# RadioMusic.net
KiCad netlist of a schematic drawn in EAGLE
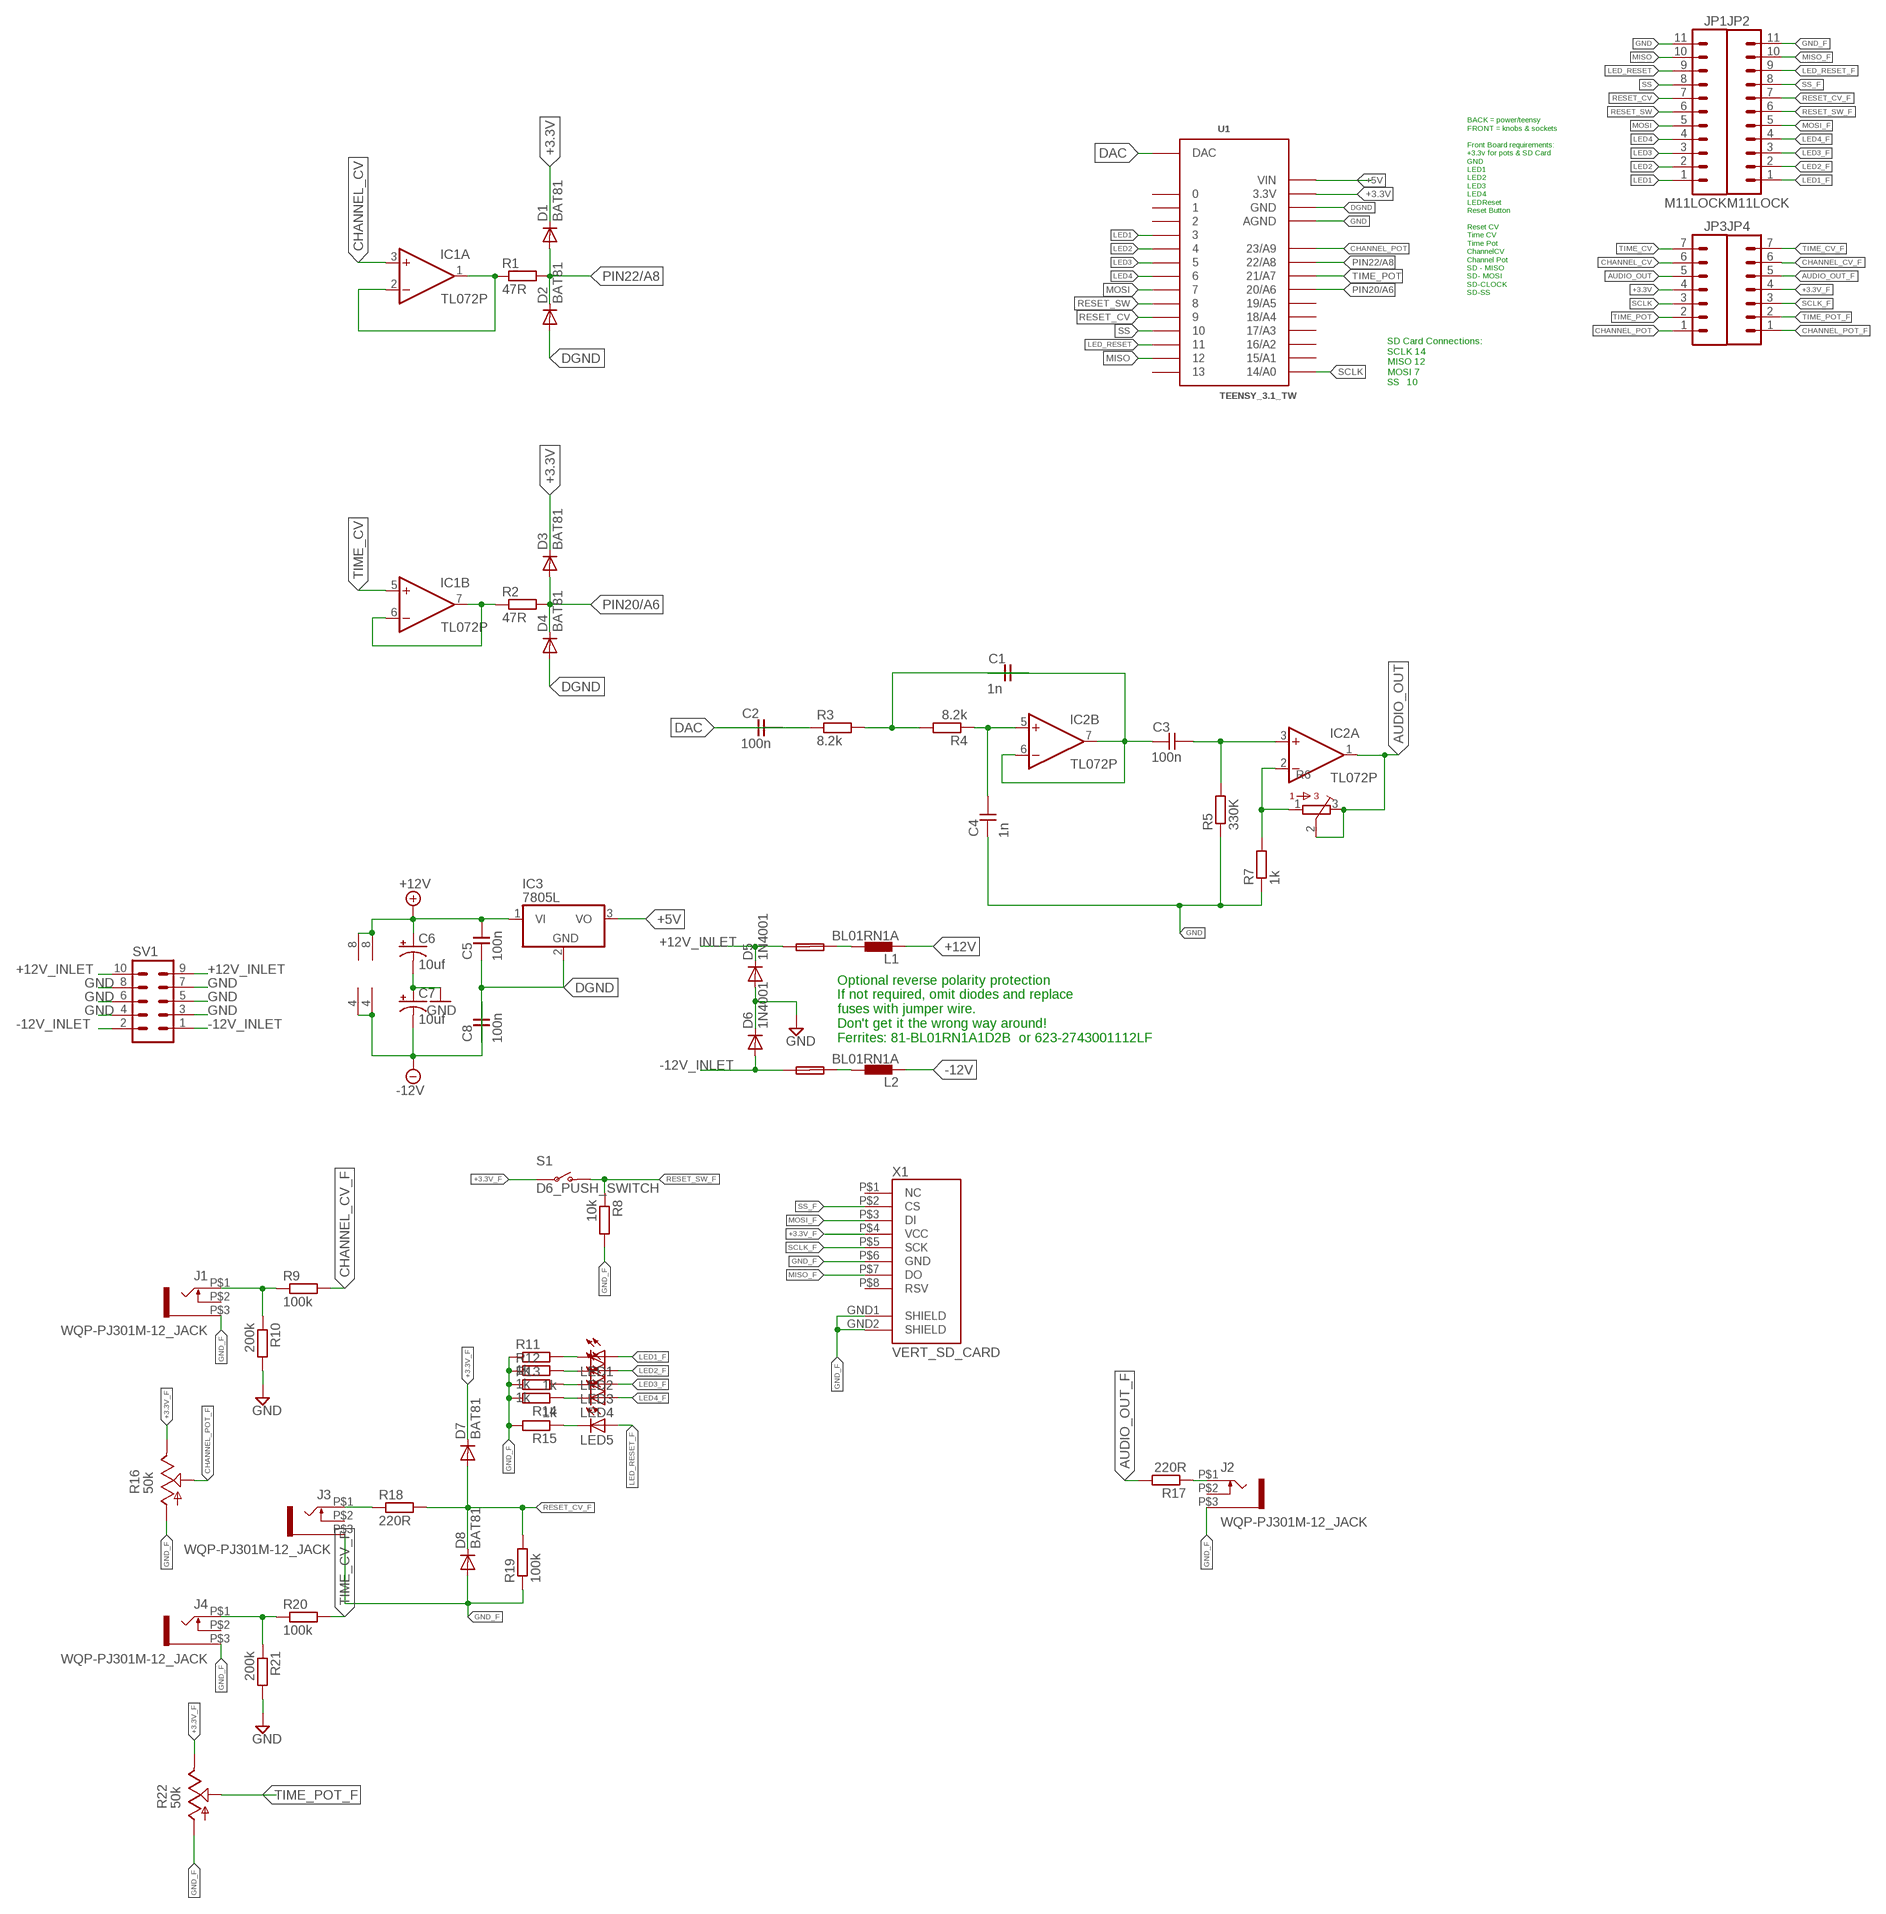
[diagram p0: schematic, sheet 1]

(export (version "E")
  (design (tool "Eeschema 10.0.6"))
  (components
    (comp (ref "C1")
      (value "1n")
      (footprint "eagle-import:C050-024X044")
      (libsource (lib "eagle-import") (part "C-EU050-024X044"))
    )
    (comp (ref "C2")
      (value "100n")
      (footprint "eagle-import:C050-025X075")
      (libsource (lib "eagle-import") (part "C-EU050-025X075"))
    )
    (comp (ref "C3")
      (value "100n")
      (footprint "eagle-import:C050-025X075")
      (libsource (lib "eagle-import") (part "C-EU050-025X075"))
    )
    (comp (ref "C4")
      (value "1n")
      (footprint "eagle-import:C050-024X044")
      (libsource (lib "eagle-import") (part "C-EU050-024X044"))
    )
    (comp (ref "C5")
      (value "100n")
      (footprint "eagle-import:C050-024X044")
      (libsource (lib "eagle-import") (part "C-EU050-024X044"))
    )
    (comp (ref "C6")
      (value "10uf")
      (footprint "eagle-import:CPOL-RADIAL-10UF-25V")
      (libsource (lib "eagle-import") (part "CAP_POLPTH2"))
    )
    (comp (ref "C7")
      (value "10uf")
      (footprint "eagle-import:CPOL-RADIAL-10UF-25V")
      (libsource (lib "eagle-import") (part "CAP_POLPTH2"))
    )
    (comp (ref "C8")
      (value "100n")
      (footprint "eagle-import:C050-024X044")
      (libsource (lib "eagle-import") (part "C-EU050-024X044"))
    )
    (comp (ref "D1")
      (value "BAT81")
      (footprint "eagle-import:DO34-7")
      (libsource (lib "eagle-import") (part "BAT81"))
    )
    (comp (ref "D2")
      (value "BAT81")
      (footprint "eagle-import:DO34-7")
      (libsource (lib "eagle-import") (part "BAT81"))
    )
    (comp (ref "D3")
      (value "BAT81")
      (footprint "eagle-import:DO34-7")
      (libsource (lib "eagle-import") (part "BAT81"))
    )
    (comp (ref "D4")
      (value "BAT81")
      (footprint "eagle-import:DO34-7")
      (libsource (lib "eagle-import") (part "BAT81"))
    )
    (comp (ref "D5")
      (value "1N4001")
      (footprint "eagle-import:DO41-10")
      (libsource (lib "eagle-import") (part "1N4004"))
    )
    (comp (ref "D6")
      (value "1N4001")
      (footprint "eagle-import:DO41-10")
      (libsource (lib "eagle-import") (part "1N4004"))
    )
    (comp (ref "D7")
      (value "BAT81")
      (footprint "eagle-import:DO34-7")
      (libsource (lib "eagle-import") (part "BAT81"))
    )
    (comp (ref "D8")
      (value "BAT81")
      (footprint "eagle-import:DO34-7")
      (libsource (lib "eagle-import") (part "BAT81"))
    )
    (comp (ref "F1")
      (value "FUSE")
      (footprint "eagle-import:C050H075X075")
      (libsource (lib "eagle-import") (part "PTC_FUSEPOLY_FUSE"))
    )
    (comp (ref "F2")
      (value "FUSE")
      (footprint "eagle-import:C050H075X075")
      (libsource (lib "eagle-import") (part "PTC_FUSEPOLY_FUSE"))
    )
    (comp (ref "IC1")
      (value "TL072P")
      (footprint "eagle-import:DIL08")
      (libsource (lib "eagle-import") (part "TL072P"))
    )
    (comp (ref "IC2")
      (value "TL072P")
      (footprint "eagle-import:DIL08")
      (libsource (lib "eagle-import") (part "TL072P"))
    )
    (comp (ref "IC3")
      (value "7805L")
      (footprint "eagle-import:TO92")
      (libsource (lib "eagle-import") (part "78L05"))
    )
    (comp (ref "J1")
      (value "WQP-PJ301M-12_JACK")
      (footprint "eagle-import:WQP-PJ301M-12_JACK")
      (libsource (lib "eagle-import") (part "WQP-PJ301M-12_JACK"))
    )
    (comp (ref "J2")
      (value "WQP-PJ301M-12_JACK")
      (footprint "eagle-import:WQP-PJ301M-12_JACK")
      (libsource (lib "eagle-import") (part "WQP-PJ301M-12_JACK"))
    )
    (comp (ref "J3")
      (value "WQP-PJ301M-12_JACK")
      (footprint "eagle-import:WQP-PJ301M-12_JACK")
      (libsource (lib "eagle-import") (part "WQP-PJ301M-12_JACK"))
    )
    (comp (ref "J4")
      (value "WQP-PJ301M-12_JACK")
      (footprint "eagle-import:WQP-PJ301M-12_JACK")
      (libsource (lib "eagle-import") (part "WQP-PJ301M-12_JACK"))
    )
    (comp (ref "JP1")
      (value "M11LOCK")
      (footprint "eagle-import:1X11_LOCK")
      (libsource (lib "eagle-import") (part "M11LOCK"))
    )
    (comp (ref "JP2")
      (value "M11LOCK")
      (footprint "eagle-import:1X11_LOCK")
      (libsource (lib "eagle-import") (part "M11LOCK"))
    )
    (comp (ref "JP3")
      (value "M07LOCK")
      (footprint "eagle-import:1X07_LOCK")
      (libsource (lib "eagle-import") (part "M07LOCK"))
    )
    (comp (ref "JP4")
      (value "M07LOCK")
      (footprint "eagle-import:1X07_LOCK")
      (libsource (lib "eagle-import") (part "M07LOCK"))
    )
    (comp (ref "L1")
      (value "BL01RN1A")
      (footprint "eagle-import:BL01RN1A")
      (libsource (lib "eagle-import") (part "BL01RN1A"))
    )
    (comp (ref "L2")
      (value "BL01RN1A")
      (footprint "eagle-import:BL01RN1A")
      (libsource (lib "eagle-import") (part "BL01RN1A"))
    )
    (comp (ref "LED1")
      (value "LED3MM")
      (footprint "eagle-import:LED3MM")
      (libsource (lib "eagle-import") (part "LED3MM"))
    )
    (comp (ref "LED2")
      (value "LED3MM")
      (footprint "eagle-import:LED3MM")
      (libsource (lib "eagle-import") (part "LED3MM"))
    )
    (comp (ref "LED3")
      (value "LED3MM")
      (footprint "eagle-import:LED3MM")
      (libsource (lib "eagle-import") (part "LED3MM"))
    )
    (comp (ref "LED4")
      (value "LED3MM")
      (footprint "eagle-import:LED3MM")
      (libsource (lib "eagle-import") (part "LED3MM"))
    )
    (comp (ref "LED5")
      (value "LED3MM")
      (footprint "eagle-import:LED3MM")
      (libsource (lib "eagle-import") (part "LED3MM"))
    )
    (comp (ref "R1")
      (value "47R")
      (footprint "eagle-import:0207_10")
      (libsource (lib "eagle-import") (part "R-EU_STANDARD_RESISTOR"))
    )
    (comp (ref "R2")
      (value "47R")
      (footprint "eagle-import:0207_10")
      (libsource (lib "eagle-import") (part "R-EU_STANDARD_RESISTOR"))
    )
    (comp (ref "R3")
      (value "8.2k")
      (footprint "eagle-import:0207_10")
      (libsource (lib "eagle-import") (part "R-EU_STANDARD_RESISTOR"))
    )
    (comp (ref "R4")
      (value "8.2k")
      (footprint "eagle-import:0207_10")
      (libsource (lib "eagle-import") (part "R-EU_STANDARD_RESISTOR"))
    )
    (comp (ref "R5")
      (value "330K")
      (footprint "eagle-import:0207_10")
      (libsource (lib "eagle-import") (part "R-EU_STANDARD_RESISTOR"))
    )
    (comp (ref "R6")
      (value "3362P")
      (footprint "eagle-import:3362P")
      (libsource (lib "eagle-import") (part "3362P"))
    )
    (comp (ref "R7")
      (value "1k")
      (footprint "eagle-import:0207_10")
      (libsource (lib "eagle-import") (part "R-EU_STANDARD_RESISTOR"))
    )
    (comp (ref "R8")
      (value "10k")
      (footprint "eagle-import:0207_10")
      (libsource (lib "eagle-import") (part "R-EU_STANDARD_RESISTOR"))
    )
    (comp (ref "R9")
      (value "100k")
      (footprint "eagle-import:0207_10")
      (libsource (lib "eagle-import") (part "R-EU_STANDARD_RESISTOR"))
    )
    (comp (ref "R10")
      (value "200k")
      (footprint "eagle-import:0207_10")
      (libsource (lib "eagle-import") (part "R-EU_STANDARD_RESISTOR"))
    )
    (comp (ref "R11")
      (value "1k")
      (footprint "eagle-import:0207_10")
      (libsource (lib "eagle-import") (part "R-EU_STANDARD_RESISTOR"))
    )
    (comp (ref "R12")
      (value "1k")
      (footprint "eagle-import:0207_10")
      (libsource (lib "eagle-import") (part "R-EU_STANDARD_RESISTOR"))
    )
    (comp (ref "R13")
      (value "1k")
      (footprint "eagle-import:0207_10")
      (libsource (lib "eagle-import") (part "R-EU_STANDARD_RESISTOR"))
    )
    (comp (ref "R14")
      (value "1k")
      (footprint "eagle-import:0207_10")
      (libsource (lib "eagle-import") (part "R-EU_STANDARD_RESISTOR"))
    )
    (comp (ref "R15")
      (value "1k")
      (footprint "eagle-import:0207_10")
      (libsource (lib "eagle-import") (part "R-EU_STANDARD_RESISTOR"))
    )
    (comp (ref "R16")
      (value "50k")
      (footprint "eagle-import:EVUF")
      (libsource (lib "eagle-import") (part "ALPHA-9MMAF2"))
    )
    (comp (ref "R17")
      (value "220R")
      (footprint "eagle-import:0207_10")
      (libsource (lib "eagle-import") (part "R-EU_STANDARD_RESISTOR"))
    )
    (comp (ref "R18")
      (value "220R")
      (footprint "eagle-import:0207_10")
      (libsource (lib "eagle-import") (part "R-EU_STANDARD_RESISTOR"))
    )
    (comp (ref "R19")
      (value "100k")
      (footprint "eagle-import:0207_10")
      (libsource (lib "eagle-import") (part "R-EU_STANDARD_RESISTOR"))
    )
    (comp (ref "R20")
      (value "100k")
      (footprint "eagle-import:0207_10")
      (libsource (lib "eagle-import") (part "R-EU_STANDARD_RESISTOR"))
    )
    (comp (ref "R21")
      (value "200k")
      (footprint "eagle-import:0207_10")
      (libsource (lib "eagle-import") (part "R-EU_STANDARD_RESISTOR"))
    )
    (comp (ref "R22")
      (value "50k")
      (footprint "eagle-import:EVUF")
      (libsource (lib "eagle-import") (part "ALPHA-9MMAF2"))
    )
    (comp (ref "S1")
      (value "D6_PUSH_SWITCH")
      (footprint "eagle-import:D6_BUTTON_RND")
      (libsource (lib "eagle-import") (part "D6_PUSH_SWITCH"))
    )
    (comp (ref "SV1")
      (value "10_PIN_HEADER")
      (footprint "eagle-import:MA05-2")
      (libsource (lib "eagle-import") (part "10_PIN_HEADER"))
    )
    (comp (ref "U1")
      (value "TEENSY_3.1_TW")
      (footprint "eagle-import:TEENSY_3.1_TW")
      (libsource (lib "eagle-import") (part "TEENSY_3.1_TW"))
    )
    (comp (ref "X1")
      (value "VERT_SD_CARD")
      (footprint "eagle-import:VERT_MICROSD")
      (libsource (lib "eagle-import") (part "VERT_SD_CARD"))
    )
  )
  (nets
    (net (code "1") (name "+3.3V") (class "Default")
      (node (ref "D1") (pin "C") (pinfunction "C_C") (pintype "passive"))
      (node (ref "D3") (pin "C") (pinfunction "C_C") (pintype "passive"))
      (node (ref "JP3") (pin "4") (pinfunction "4_4") (pintype "passive"))
      (node (ref "U1") (pin "3.3V") (pinfunction "3.3V_3.3V") (pintype "power_in"))
    )
    (net (code "2") (name "+3.3V_F") (class "Default")
      (node (ref "D7") (pin "C") (pinfunction "C_C") (pintype "passive"))
      (node (ref "JP4") (pin "4") (pinfunction "4_4") (pintype "passive"))
      (node (ref "R16") (pin "3") (pinfunction "E_3") (pintype "passive"))
      (node (ref "R22") (pin "3") (pinfunction "E_3") (pintype "passive"))
      (node (ref "S1") (pin "P$3") (pinfunction "P_P$3") (pintype "passive"))
      (node (ref "S1") (pin "P$4") (pinfunction "P_P$4") (pintype "passive"))
      (node (ref "X1") (pin "P$4") (pinfunction "VCC_P$4") (pintype "bidirectional"))
    )
    (net (code "3") (name "+5V") (class "Default")
      (node (ref "IC3") (pin "3") (pinfunction "VO_3") (pintype "passive"))
      (node (ref "U1") (pin "VIN") (pinfunction "VIN_VIN") (pintype "power_in"))
    )
    (net (code "4") (name "+12V") (class "Default")
      (node (ref "C5") (pin "1") (pinfunction "1_1") (pintype "passive"))
      (node (ref "C6") (pin "1") (pinfunction "+_1") (pintype "passive"))
      (node (ref "IC1") (pin "8") (pinfunction "V+_8") (pintype "power_in"))
      (node (ref "IC2") (pin "8") (pinfunction "V+_8") (pintype "power_in"))
      (node (ref "IC3") (pin "1") (pinfunction "VI_1") (pintype "input"))
      (node (ref "L1") (pin "1") (pinfunction "1_1") (pintype "passive"))
    )
    (net (code "5") (name "-12V") (class "Default")
      (node (ref "C7") (pin "2") (pinfunction "-_2") (pintype "passive"))
      (node (ref "C8") (pin "1") (pinfunction "1_1") (pintype "passive"))
      (node (ref "IC1") (pin "4") (pinfunction "V-_4") (pintype "power_in"))
      (node (ref "IC2") (pin "4") (pinfunction "V-_4") (pintype "power_in"))
      (node (ref "L2") (pin "1") (pinfunction "1_1") (pintype "passive"))
    )
    (net (code "6") (name "/+12V_INLET") (class "Default")
      (node (ref "D5") (pin "C") (pinfunction "C_C") (pintype "passive"))
      (node (ref "F1") (pin "1") (pinfunction "P$1_1") (pintype "bidirectional"))
      (node (ref "SV1") (pin "10") (pinfunction "10_10") (pintype "passive"))
      (node (ref "SV1") (pin "9") (pinfunction "9_9") (pintype "passive"))
    )
    (net (code "7") (name "/-12V_INLET") (class "Default")
      (node (ref "D6") (pin "A") (pinfunction "A_A") (pintype "passive"))
      (node (ref "F2") (pin "1") (pinfunction "P$1_1") (pintype "bidirectional"))
      (node (ref "SV1") (pin "1") (pinfunction "1_1") (pintype "passive"))
      (node (ref "SV1") (pin "2") (pinfunction "2_2") (pintype "passive"))
    )
    (net (code "8") (name "AUDIO_OUT") (class "Default")
      (node (ref "IC2") (pin "1") (pinfunction "OUT_1") (pintype "output"))
      (node (ref "JP3") (pin "5") (pinfunction "5_5") (pintype "passive"))
      (node (ref "R6") (pin "2") (pinfunction "2_2") (pintype "passive"))
      (node (ref "R6") (pin "3") (pinfunction "3_3") (pintype "passive"))
    )
    (net (code "9") (name "AUDIO_OUT_F") (class "Default")
      (node (ref "JP4") (pin "5") (pinfunction "5_5") (pintype "passive"))
      (node (ref "R17") (pin "2") (pinfunction "2_2") (pintype "passive"))
    )
    (net (code "10") (name "CHANNEL_CV") (class "Default")
      (node (ref "IC1") (pin "3") (pinfunction "+IN_3") (pintype "input"))
      (node (ref "JP3") (pin "6") (pinfunction "6_6") (pintype "passive"))
    )
    (net (code "11") (name "CHANNEL_CV_F") (class "Default")
      (node (ref "JP4") (pin "6") (pinfunction "6_6") (pintype "passive"))
      (node (ref "R9") (pin "2") (pinfunction "2_2") (pintype "passive"))
    )
    (net (code "12") (name "CHANNEL_POT") (class "Default")
      (node (ref "JP3") (pin "1") (pinfunction "1_1") (pintype "passive"))
      (node (ref "U1") (pin "23/A9") (pinfunction "23/A9_23/A9") (pintype "bidirectional"))
    )
    (net (code "13") (name "CHANNEL_POT_F") (class "Default")
      (node (ref "JP4") (pin "1") (pinfunction "1_1") (pintype "passive"))
      (node (ref "R16") (pin "2") (pinfunction "S_2") (pintype "passive"))
    )
    (net (code "14") (name "DAC") (class "Default")
      (node (ref "C2") (pin "1") (pinfunction "1_1") (pintype "passive"))
      (node (ref "U1") (pin "DAC") (pinfunction "DAC_DAC") (pintype "bidirectional"))
    )
    (net (code "15") (name "DGND") (class "Default")
      (node (ref "C5") (pin "2") (pinfunction "2_2") (pintype "passive"))
      (node (ref "C8") (pin "2") (pinfunction "2_2") (pintype "passive"))
      (node (ref "D2") (pin "A") (pinfunction "A_A") (pintype "passive"))
      (node (ref "D4") (pin "A") (pinfunction "A_A") (pintype "passive"))
      (node (ref "IC3") (pin "2") (pinfunction "GND_2") (pintype "passive"))
      (node (ref "U1") (pin "GND") (pinfunction "GND_GND") (pintype "power_in"))
    )
    (net (code "16") (name "GND") (class "Default")
      (node (ref "C4") (pin "2") (pinfunction "2_2") (pintype "passive"))
      (node (ref "C6") (pin "2") (pinfunction "-_2") (pintype "passive"))
      (node (ref "C7") (pin "1") (pinfunction "+_1") (pintype "passive"))
      (node (ref "D5") (pin "A") (pinfunction "A_A") (pintype "passive"))
      (node (ref "D6") (pin "C") (pinfunction "C_C") (pintype "passive"))
      (node (ref "JP1") (pin "11") (pinfunction "11_11") (pintype "passive"))
      (node (ref "R10") (pin "2") (pinfunction "2_2") (pintype "passive"))
      (node (ref "R21") (pin "2") (pinfunction "2_2") (pintype "passive"))
      (node (ref "R5") (pin "1") (pinfunction "1_1") (pintype "passive"))
      (node (ref "R7") (pin "1") (pinfunction "1_1") (pintype "passive"))
      (node (ref "SV1") (pin "3") (pinfunction "3_3") (pintype "passive"))
      (node (ref "SV1") (pin "4") (pinfunction "4_4") (pintype "passive"))
      (node (ref "SV1") (pin "5") (pinfunction "5_5") (pintype "passive"))
      (node (ref "SV1") (pin "6") (pinfunction "6_6") (pintype "passive"))
      (node (ref "SV1") (pin "7") (pinfunction "7_7") (pintype "passive"))
      (node (ref "SV1") (pin "8") (pinfunction "8_8") (pintype "passive"))
      (node (ref "U1") (pin "AGND") (pinfunction "AGND_AGND") (pintype "power_in"))
    )
    (net (code "17") (name "GND_F") (class "Default")
      (node (ref "D8") (pin "A") (pinfunction "A_A") (pintype "passive"))
      (node (ref "J1") (pin "P$3") (pinfunction "1_P$3") (pintype "passive"))
      (node (ref "J2") (pin "P$3") (pinfunction "1_P$3") (pintype "passive"))
      (node (ref "J3") (pin "P$3") (pinfunction "1_P$3") (pintype "passive"))
      (node (ref "J4") (pin "P$3") (pinfunction "1_P$3") (pintype "passive"))
      (node (ref "JP2") (pin "11") (pinfunction "11_11") (pintype "passive"))
      (node (ref "R11") (pin "1") (pinfunction "1_1") (pintype "passive"))
      (node (ref "R12") (pin "1") (pinfunction "1_1") (pintype "passive"))
      (node (ref "R13") (pin "1") (pinfunction "1_1") (pintype "passive"))
      (node (ref "R14") (pin "2") (pinfunction "2_2") (pintype "passive"))
      (node (ref "R15") (pin "2") (pinfunction "2_2") (pintype "passive"))
      (node (ref "R16") (pin "1") (pinfunction "A_1") (pintype "passive"))
      (node (ref "R19") (pin "1") (pinfunction "1_1") (pintype "passive"))
      (node (ref "R22") (pin "1") (pinfunction "A_1") (pintype "passive"))
      (node (ref "R8") (pin "2") (pinfunction "2_2") (pintype "passive"))
      (node (ref "X1") (pin "GND1") (pinfunction "SHIELD_GND1") (pintype "bidirectional"))
      (node (ref "X1") (pin "GND2") (pinfunction "SHIELD_GND2") (pintype "bidirectional"))
      (node (ref "X1") (pin "P$6") (pinfunction "GND_P$6") (pintype "bidirectional"))
    )
    (net (code "18") (name "LED1") (class "Default")
      (node (ref "JP1") (pin "1") (pinfunction "1_1") (pintype "passive"))
      (node (ref "U1") (pin "3") (pinfunction "3_3") (pintype "bidirectional"))
    )
    (net (code "19") (name "LED1_F") (class "Default")
      (node (ref "JP2") (pin "1") (pinfunction "1_1") (pintype "passive"))
      (node (ref "LED1") (pin "A") (pinfunction "A_A") (pintype "passive"))
    )
    (net (code "20") (name "LED2") (class "Default")
      (node (ref "JP1") (pin "2") (pinfunction "2_2") (pintype "passive"))
      (node (ref "U1") (pin "4") (pinfunction "4_4") (pintype "bidirectional"))
    )
    (net (code "21") (name "LED2_F") (class "Default")
      (node (ref "JP2") (pin "2") (pinfunction "2_2") (pintype "passive"))
      (node (ref "LED2") (pin "A") (pinfunction "A_A") (pintype "passive"))
    )
    (net (code "22") (name "LED3") (class "Default")
      (node (ref "JP1") (pin "3") (pinfunction "3_3") (pintype "passive"))
      (node (ref "U1") (pin "5") (pinfunction "5_5") (pintype "bidirectional"))
    )
    (net (code "23") (name "LED3_F") (class "Default")
      (node (ref "JP2") (pin "3") (pinfunction "3_3") (pintype "passive"))
      (node (ref "LED3") (pin "A") (pinfunction "A_A") (pintype "passive"))
    )
    (net (code "24") (name "LED4") (class "Default")
      (node (ref "JP1") (pin "4") (pinfunction "4_4") (pintype "passive"))
      (node (ref "U1") (pin "6") (pinfunction "6_6") (pintype "bidirectional"))
    )
    (net (code "25") (name "LED4_F") (class "Default")
      (node (ref "JP2") (pin "4") (pinfunction "4_4") (pintype "passive"))
      (node (ref "LED4") (pin "A") (pinfunction "A_A") (pintype "passive"))
    )
    (net (code "26") (name "LED_RESET") (class "Default")
      (node (ref "JP1") (pin "9") (pinfunction "9_9") (pintype "passive"))
      (node (ref "U1") (pin "11") (pinfunction "11_11") (pintype "bidirectional"))
    )
    (net (code "27") (name "LED_RESET_F") (class "Default")
      (node (ref "JP2") (pin "9") (pinfunction "9_9") (pintype "passive"))
      (node (ref "LED5") (pin "A") (pinfunction "A_A") (pintype "passive"))
    )
    (net (code "28") (name "MISO") (class "Default")
      (node (ref "JP1") (pin "10") (pinfunction "10_10") (pintype "passive"))
      (node (ref "U1") (pin "12") (pinfunction "12_12") (pintype "bidirectional"))
    )
    (net (code "29") (name "MISO_F") (class "Default")
      (node (ref "JP2") (pin "10") (pinfunction "10_10") (pintype "passive"))
      (node (ref "X1") (pin "P$7") (pinfunction "DO_P$7") (pintype "bidirectional"))
    )
    (net (code "30") (name "MOSI") (class "Default")
      (node (ref "JP1") (pin "5") (pinfunction "5_5") (pintype "passive"))
      (node (ref "U1") (pin "7") (pinfunction "7_7") (pintype "bidirectional"))
    )
    (net (code "31") (name "MOSI_F") (class "Default")
      (node (ref "JP2") (pin "5") (pinfunction "5_5") (pintype "passive"))
      (node (ref "X1") (pin "P$3") (pinfunction "DI_P$3") (pintype "bidirectional"))
    )
    (net (code "32") (name "Net-(C1-Pad1)") (class "Default")
      (node (ref "C1") (pin "1") (pinfunction "1_1") (pintype "passive"))
      (node (ref "R3") (pin "2") (pinfunction "2_2") (pintype "passive"))
      (node (ref "R4") (pin "2") (pinfunction "2_2") (pintype "passive"))
    )
    (net (code "33") (name "Net-(C2-Pad2)") (class "Default")
      (node (ref "C2") (pin "2") (pinfunction "2_2") (pintype "passive"))
      (node (ref "R3") (pin "1") (pinfunction "1_1") (pintype "passive"))
    )
    (net (code "34") (name "Net-(F1-P$2)") (class "Default")
      (node (ref "F1") (pin "2") (pinfunction "P$2_2") (pintype "bidirectional"))
      (node (ref "L1") (pin "2") (pinfunction "2_2") (pintype "passive"))
    )
    (net (code "35") (name "Net-(F2-P$2)") (class "Default")
      (node (ref "F2") (pin "2") (pinfunction "P$2_2") (pintype "bidirectional"))
      (node (ref "L2") (pin "2") (pinfunction "2_2") (pintype "passive"))
    )
    (net (code "36") (name "Net-(IC1B--IN)") (class "Default")
      (node (ref "IC1") (pin "6") (pinfunction "-IN_6") (pintype "input"))
      (node (ref "IC1") (pin "7") (pinfunction "OUT_7") (pintype "output"))
      (node (ref "R2") (pin "1") (pinfunction "1_1") (pintype "passive"))
    )
    (net (code "37") (name "Net-(IC2A-+IN)") (class "Default")
      (node (ref "C3") (pin "1") (pinfunction "1_1") (pintype "passive"))
      (node (ref "IC2") (pin "3") (pinfunction "+IN_3") (pintype "input"))
      (node (ref "R5") (pin "2") (pinfunction "2_2") (pintype "passive"))
    )
    (net (code "38") (name "Net-(IC2A--IN)") (class "Default")
      (node (ref "IC2") (pin "2") (pinfunction "-IN_2") (pintype "input"))
      (node (ref "R6") (pin "1") (pinfunction "1_1") (pintype "passive"))
      (node (ref "R7") (pin "2") (pinfunction "2_2") (pintype "passive"))
    )
    (net (code "39") (name "Net-(IC2B-+IN)") (class "Default")
      (node (ref "C4") (pin "1") (pinfunction "1_1") (pintype "passive"))
      (node (ref "IC2") (pin "5") (pinfunction "+IN_5") (pintype "input"))
      (node (ref "R4") (pin "1") (pinfunction "1_1") (pintype "passive"))
    )
    (net (code "40") (name "Net-(IC2B--IN)") (class "Default")
      (node (ref "C1") (pin "2") (pinfunction "2_2") (pintype "passive"))
      (node (ref "C3") (pin "2") (pinfunction "2_2") (pintype "passive"))
      (node (ref "IC2") (pin "6") (pinfunction "-IN_6") (pintype "input"))
      (node (ref "IC2") (pin "7") (pinfunction "OUT_7") (pintype "output"))
    )
    (net (code "41") (name "Net-(J1-2)") (class "Default")
      (node (ref "J1") (pin "P$1") (pinfunction "2_P$1") (pintype "passive"))
      (node (ref "R10") (pin "1") (pinfunction "1_1") (pintype "passive"))
      (node (ref "R9") (pin "1") (pinfunction "1_1") (pintype "passive"))
    )
    (net (code "42") (name "Net-(J2-2)") (class "Default")
      (node (ref "J2") (pin "P$1") (pinfunction "2_P$1") (pintype "passive"))
      (node (ref "R17") (pin "1") (pinfunction "1_1") (pintype "passive"))
    )
    (net (code "43") (name "Net-(J3-2)") (class "Default")
      (node (ref "J3") (pin "P$1") (pinfunction "2_P$1") (pintype "passive"))
      (node (ref "R18") (pin "1") (pinfunction "1_1") (pintype "passive"))
    )
    (net (code "44") (name "Net-(J4-2)") (class "Default")
      (node (ref "J4") (pin "P$1") (pinfunction "2_P$1") (pintype "passive"))
      (node (ref "R20") (pin "1") (pinfunction "1_1") (pintype "passive"))
      (node (ref "R21") (pin "1") (pinfunction "1_1") (pintype "passive"))
    )
    (net (code "45") (name "Net-(LED1-C)") (class "Default")
      (node (ref "LED1") (pin "K") (pinfunction "C_K") (pintype "passive"))
      (node (ref "R11") (pin "2") (pinfunction "2_2") (pintype "passive"))
    )
    (net (code "46") (name "Net-(LED2-C)") (class "Default")
      (node (ref "LED2") (pin "K") (pinfunction "C_K") (pintype "passive"))
      (node (ref "R12") (pin "2") (pinfunction "2_2") (pintype "passive"))
    )
    (net (code "47") (name "Net-(LED3-C)") (class "Default")
      (node (ref "LED3") (pin "K") (pinfunction "C_K") (pintype "passive"))
      (node (ref "R13") (pin "2") (pinfunction "2_2") (pintype "passive"))
    )
    (net (code "48") (name "Net-(LED4-C)") (class "Default")
      (node (ref "LED4") (pin "K") (pinfunction "C_K") (pintype "passive"))
      (node (ref "R14") (pin "1") (pinfunction "1_1") (pintype "passive"))
    )
    (net (code "49") (name "Net-(LED5-C)") (class "Default")
      (node (ref "LED5") (pin "K") (pinfunction "C_K") (pintype "passive"))
      (node (ref "R15") (pin "1") (pinfunction "1_1") (pintype "passive"))
    )
    (net (code "50") (name "PIN20{slash}A6") (class "Default")
      (node (ref "D3") (pin "A") (pinfunction "A_A") (pintype "passive"))
      (node (ref "D4") (pin "C") (pinfunction "C_C") (pintype "passive"))
      (node (ref "R2") (pin "2") (pinfunction "2_2") (pintype "passive"))
      (node (ref "U1") (pin "20/A6") (pinfunction "20/A6_20/A6") (pintype "bidirectional"))
    )
    (net (code "51") (name "PIN22{slash}A8") (class "Default")
      (node (ref "D1") (pin "A") (pinfunction "A_A") (pintype "passive"))
      (node (ref "D2") (pin "C") (pinfunction "C_C") (pintype "passive"))
      (node (ref "IC1") (pin "1") (pinfunction "OUT_1") (pintype "output"))
      (node (ref "IC1") (pin "2") (pinfunction "-IN_2") (pintype "input"))
      (node (ref "R1") (pin "1") (pinfunction "1_1") (pintype "passive"))
      (node (ref "R1") (pin "2") (pinfunction "2_2") (pintype "passive"))
      (node (ref "U1") (pin "22/A8") (pinfunction "22/A8_22/A8") (pintype "bidirectional"))
    )
    (net (code "52") (name "RESET_CV") (class "Default")
      (node (ref "JP1") (pin "7") (pinfunction "7_7") (pintype "passive"))
      (node (ref "U1") (pin "9") (pinfunction "9_9") (pintype "bidirectional"))
    )
    (net (code "53") (name "RESET_CV_F") (class "Default")
      (node (ref "D7") (pin "A") (pinfunction "A_A") (pintype "passive"))
      (node (ref "D8") (pin "C") (pinfunction "C_C") (pintype "passive"))
      (node (ref "JP2") (pin "7") (pinfunction "7_7") (pintype "passive"))
      (node (ref "R18") (pin "2") (pinfunction "2_2") (pintype "passive"))
      (node (ref "R19") (pin "2") (pinfunction "2_2") (pintype "passive"))
    )
    (net (code "54") (name "RESET_SW") (class "Default")
      (node (ref "JP1") (pin "6") (pinfunction "6_6") (pintype "passive"))
      (node (ref "U1") (pin "8") (pinfunction "8_8") (pintype "bidirectional"))
    )
    (net (code "55") (name "RESET_SW_F") (class "Default")
      (node (ref "JP2") (pin "6") (pinfunction "6_6") (pintype "passive"))
      (node (ref "R8") (pin "1") (pinfunction "1_1") (pintype "passive"))
      (node (ref "S1") (pin "P$1") (pinfunction "O_P$1") (pintype "passive"))
      (node (ref "S1") (pin "P$2") (pinfunction "O_P$2") (pintype "passive"))
    )
    (net (code "56") (name "SCLK") (class "Default")
      (node (ref "JP3") (pin "3") (pinfunction "3_3") (pintype "passive"))
      (node (ref "U1") (pin "14/A0") (pinfunction "14/A0_14/A0") (pintype "bidirectional"))
    )
    (net (code "57") (name "SCLK_F") (class "Default")
      (node (ref "JP4") (pin "3") (pinfunction "3_3") (pintype "passive"))
      (node (ref "X1") (pin "P$5") (pinfunction "SCK_P$5") (pintype "bidirectional"))
    )
    (net (code "58") (name "SS") (class "Default")
      (node (ref "JP1") (pin "8") (pinfunction "8_8") (pintype "passive"))
      (node (ref "U1") (pin "10") (pinfunction "10_10") (pintype "bidirectional"))
    )
    (net (code "59") (name "SS_F") (class "Default")
      (node (ref "JP2") (pin "8") (pinfunction "8_8") (pintype "passive"))
      (node (ref "X1") (pin "P$2") (pinfunction "CS_P$2") (pintype "bidirectional"))
    )
    (net (code "60") (name "TIME_CV") (class "Default")
      (node (ref "IC1") (pin "5") (pinfunction "+IN_5") (pintype "input"))
      (node (ref "JP3") (pin "7") (pinfunction "7_7") (pintype "passive"))
    )
    (net (code "61") (name "TIME_CV_F") (class "Default")
      (node (ref "JP4") (pin "7") (pinfunction "7_7") (pintype "passive"))
      (node (ref "R20") (pin "2") (pinfunction "2_2") (pintype "passive"))
    )
    (net (code "62") (name "TIME_POT") (class "Default")
      (node (ref "JP3") (pin "2") (pinfunction "2_2") (pintype "passive"))
      (node (ref "U1") (pin "21/A7") (pinfunction "21/A7_21/A7") (pintype "bidirectional"))
    )
    (net (code "63") (name "TIME_POT_F") (class "Default")
      (node (ref "JP4") (pin "2") (pinfunction "2_2") (pintype "passive"))
      (node (ref "R22") (pin "2") (pinfunction "S_2") (pintype "passive"))
    )
    (net (code "64") (name "unconnected-(J1-3-PadP$2)") (class "Default")
      (node (ref "J1") (pin "P$2") (pinfunction "3_P$2") (pintype "passive"))
    )
    (net (code "65") (name "unconnected-(J2-3-PadP$2)") (class "Default")
      (node (ref "J2") (pin "P$2") (pinfunction "3_P$2") (pintype "passive"))
    )
    (net (code "66") (name "unconnected-(J3-3-PadP$2)") (class "Default")
      (node (ref "J3") (pin "P$2") (pinfunction "3_P$2") (pintype "passive"))
    )
    (net (code "67") (name "unconnected-(J4-3-PadP$2)") (class "Default")
      (node (ref "J4") (pin "P$2") (pinfunction "3_P$2") (pintype "passive"))
    )
    (net (code "68") (name "unconnected-(U1-Pad0)") (class "Default")
      (node (ref "U1") (pin "0") (pinfunction "0_0") (pintype "bidirectional"))
    )
    (net (code "69") (name "unconnected-(U1-Pad1)") (class "Default")
      (node (ref "U1") (pin "1") (pinfunction "1_1") (pintype "bidirectional"))
    )
    (net (code "70") (name "unconnected-(U1-Pad2)") (class "Default")
      (node (ref "U1") (pin "2") (pinfunction "2_2") (pintype "bidirectional"))
    )
    (net (code "71") (name "unconnected-(U1-Pad13)") (class "Default")
      (node (ref "U1") (pin "13") (pinfunction "13_13") (pintype "bidirectional"))
    )
    (net (code "72") (name "unconnected-(U1-Pad15{slash}A1)") (class "Default")
      (node (ref "U1") (pin "15/A1") (pinfunction "15/A1_15/A1") (pintype "bidirectional"))
    )
    (net (code "73") (name "unconnected-(U1-Pad16{slash}A2)") (class "Default")
      (node (ref "U1") (pin "16/A2") (pinfunction "16/A2_16/A2") (pintype "bidirectional"))
    )
    (net (code "74") (name "unconnected-(U1-Pad17{slash}A3)") (class "Default")
      (node (ref "U1") (pin "17/A3") (pinfunction "17/A3_17/A3") (pintype "bidirectional"))
    )
    (net (code "75") (name "unconnected-(U1-Pad18{slash}A4)") (class "Default")
      (node (ref "U1") (pin "18/A4") (pinfunction "18/A4_18/A4") (pintype "bidirectional"))
    )
    (net (code "76") (name "unconnected-(U1-Pad19{slash}A5)") (class "Default")
      (node (ref "U1") (pin "19/A5") (pinfunction "19/A5_19/A5") (pintype "bidirectional"))
    )
    (net (code "77") (name "unconnected-(X1-NC-PadP$1)") (class "Default")
      (node (ref "X1") (pin "P$1") (pinfunction "NC_P$1") (pintype "bidirectional"))
    )
    (net (code "78") (name "unconnected-(X1-RSV-PadP$8)") (class "Default")
      (node (ref "X1") (pin "P$8") (pinfunction "RSV_P$8") (pintype "bidirectional"))
    )
  )
)
